# SbusConverter_v2.net
KiCad netlist of a schematic drawn in Altium Designer
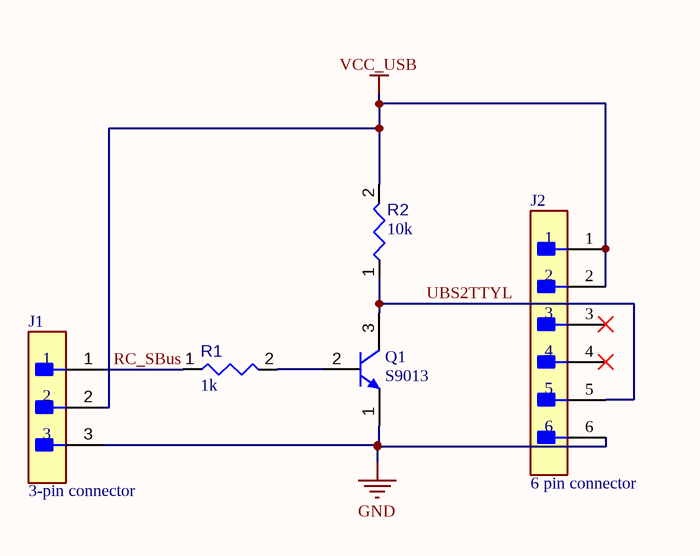
[diagram p0: SbusConverter_v2.SchDoc]

(export (version "E")
  (design (tool "Eeschema 10.0.6"))
  (components
    (comp (ref "J1")
      (value "3-pin connector")
      (footprint "FP-87224-3-MFG")
      (libsource (lib "Isae-Supaero") (part "0d3f023dd272f625e17a2be33dea85f"))
    )
    (comp (ref "J2")
      (value "6 pin connector")
      (footprint "FP-HTSW-106-07-G-S-MFG")
      (libsource (lib "Isae-Supaero") (part "f2cb566baf1c37ab5a3b8e90bbeafd6"))
    )
    (comp (ref "Q1")
      (value "S9013")
      (footprint "JSCJ-TO-92-3_V")
      (description "Transistor, NPN, 0.1 uA, 150 MHz, 3-Pin TO-92")
      (fields (field (name "MANUFACTURER") "Jiangsu Changjiang Electronics Technology"))
      (libsource (lib "Isae-Supaero") (part "BJT-NPN-EBC-3"))
    )
    (comp (ref "R1")
      (value "1k")
      (footprint "RESA60-630X240")
      (description "Axial Resistor, 1 KOhm, +/- 1%, 250 mW, -55 to 155 degC, 2-Pin THD, RoHS, Bulk")
      (fields (field (name "TOLERANCE") "1%") (field (name "POWER") "250mW"))
      (libsource (lib "Isae-Supaero") (part "RES-2"))
    )
    (comp (ref "R2")
      (value "10k")
      (footprint "RESA60-630X240")
      (description "Axial Resistor, 10 KOhm, +/- 1%, 0.25 W, -55 to 155 degC, 2-Pin THD, RoHS, Bulk")
      (fields (field (name "TOLERANCE") "1%") (field (name "POWER") "250mW"))
      (libsource (lib "Isae-Supaero") (part "RES-2"))
    )
  )
  (nets
    (net (code "1") (name "/RC_SBus") (class "Default")
      (node (ref "J1") (pin "1") (pinfunction "1_1") (pintype "passive"))
      (node (ref "R1") (pin "1") (pinfunction "1_1") (pintype "passive"))
    )
    (net (code "2") (name "/UBS2TTYL") (class "Default")
      (node (ref "J2") (pin "5") (pinfunction "5_5") (pintype "passive"))
      (node (ref "Q1") (pin "3") (pinfunction "C_3") (pintype "passive"))
      (node (ref "R2") (pin "1") (pinfunction "1_1") (pintype "passive"))
    )
    (net (code "3") (name "GND") (class "Default")
      (node (ref "J1") (pin "3") (pinfunction "3_3") (pintype "passive"))
      (node (ref "J2") (pin "6") (pinfunction "6_6") (pintype "passive"))
      (node (ref "Q1") (pin "1") (pinfunction "E_1") (pintype "passive"))
    )
    (net (code "4") (name "Net-(Q1-B)") (class "Default")
      (node (ref "Q1") (pin "2") (pinfunction "B_2") (pintype "passive"))
      (node (ref "R1") (pin "2") (pinfunction "2_2") (pintype "passive"))
    )
    (net (code "5") (name "VCC_USB") (class "Default")
      (node (ref "J1") (pin "2") (pinfunction "2_2") (pintype "passive"))
      (node (ref "J2") (pin "1") (pinfunction "1_1") (pintype "passive"))
      (node (ref "J2") (pin "2") (pinfunction "2_2") (pintype "passive"))
      (node (ref "R2") (pin "2") (pinfunction "2_2") (pintype "passive"))
    )
    (net (code "6") (name "unconnected-(J2-Pad3)") (class "Default")
      (node (ref "J2") (pin "3") (pinfunction "3_3") (pintype "passive+no_connect"))
    )
    (net (code "7") (name "unconnected-(J2-Pad4)") (class "Default")
      (node (ref "J2") (pin "4") (pinfunction "4_4") (pintype "passive+no_connect"))
    )
  )
)
